# UBC-Thunderbots_PCB_Power__archive_power.net
KiCad netlist of a schematic drawn in Altium Designer
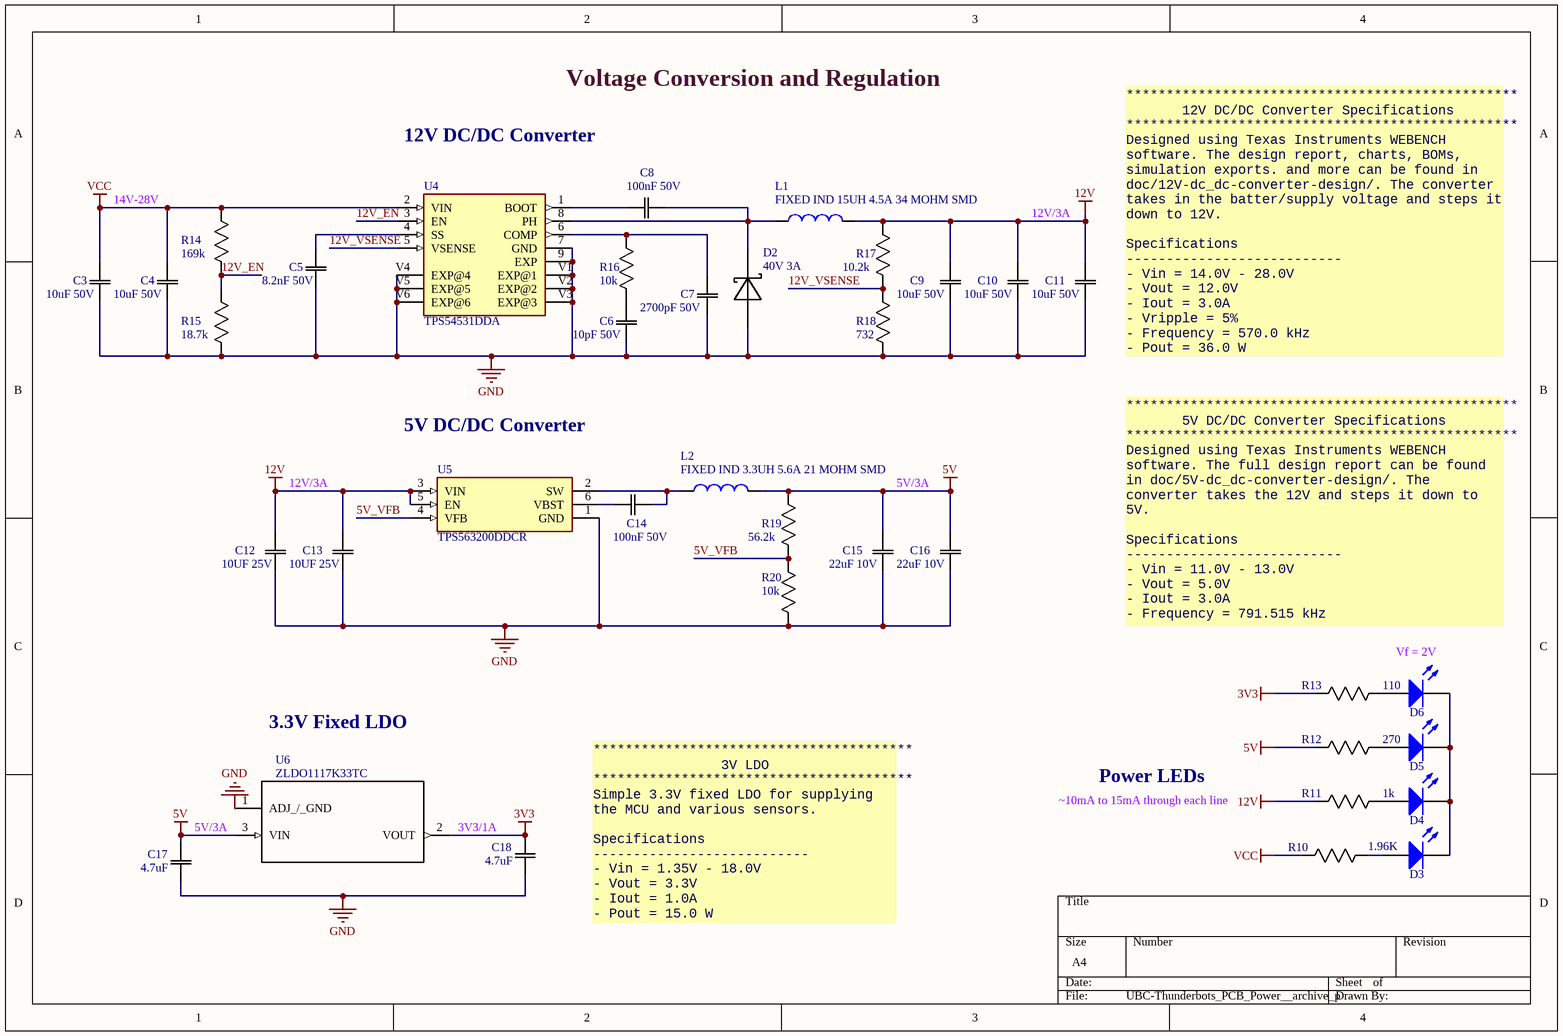
[diagram p0: UBC-Thunderbots_PCB_Power__archive_power-v2.1_pcb__regulation.SchDoc]

(export (version "E")
  (design (tool "Eeschema 10.0.6"))
  (components
    (comp (ref "C3")
      (value "10uF 50V")
      (footprint "1210")
      (description "CAP CER 10UF 50V X7R")
      (fields (field (name "TOLERANCE") "10%"))
      (libsource (lib "AltiumLibraries") (part "CAP 10uF 50V"))
    )
    (comp (ref "C4")
      (value "10uF 50V")
      (footprint "1210")
      (description "CAP CER 10UF 50V X7R")
      (fields (field (name "TOLERANCE") "10%"))
      (libsource (lib "AltiumLibraries") (part "CAP 10uF 50V"))
    )
    (comp (ref "C5")
      (value "8.2nF 50V")
      (footprint "0805")
      (description "CAP CER 8200PF 50V X7R 0805")
      (fields (field (name "TOLERANCE") "10%"))
      (libsource (lib "AltiumLibraries") (part "CAP 8.2nF 50V"))
    )
    (comp (ref "C6")
      (value "10pF 50V")
      (footprint "0603")
      (description "CAP CER 10PF 50V X7R 0603")
      (fields (field (name "TOLERANCE") "10%"))
      (libsource (lib "AltiumLibraries") (part "CAP 10pF 50V"))
    )
    (comp (ref "C7")
      (value "2700pF 50V")
      (footprint "0805")
      (description "CAP CER 2700PF 50V X7R 0805")
      (fields (field (name "TOLERANCE") "10%"))
      (libsource (lib "AltiumLibraries") (part "CAP 2700pF 50V"))
    )
    (comp (ref "C8")
      (value "100nF 50V")
      (footprint "0805")
      (description "CAP CER 0.1UF 50V X7R 0805")
      (fields (field (name "TOLERANCE") "10%"))
      (libsource (lib "AltiumLibraries") (part "CAP 100nF 50V"))
    )
    (comp (ref "C9")
      (value "10uF 50V")
      (footprint "1210")
      (description "CAP CER 10UF 50V X7R")
      (fields (field (name "TOLERANCE") "10%"))
      (libsource (lib "AltiumLibraries") (part "CAP 10uF 50V"))
    )
    (comp (ref "C10")
      (value "10uF 50V")
      (footprint "1210")
      (description "CAP CER 10UF 50V X7R")
      (fields (field (name "TOLERANCE") "10%"))
      (libsource (lib "AltiumLibraries") (part "CAP 10uF 50V"))
    )
    (comp (ref "C11")
      (value "10uF 50V")
      (footprint "1210")
      (description "CAP CER 10UF 50V X7R")
      (fields (field (name "TOLERANCE") "10%"))
      (libsource (lib "AltiumLibraries") (part "CAP 10uF 50V"))
    )
    (comp (ref "C12")
      (value "10UF 25V")
      (footprint "1206")
      (description "CAP CER 10UF 25V X5R 1206")
      (fields (field (name "TOLERANCE") "10%"))
      (libsource (lib "AltiumLibraries") (part "CAP 10uF 25V"))
    )
    (comp (ref "C13")
      (value "10UF 25V")
      (footprint "1206")
      (description "CAP CER 10UF 25V X5R 1206")
      (fields (field (name "TOLERANCE") "10%"))
      (libsource (lib "AltiumLibraries") (part "CAP 10uF 25V"))
    )
    (comp (ref "C14")
      (value "100nF 50V")
      (footprint "0805")
      (description "CAP CER 0.1UF 50V X7R 0805")
      (fields (field (name "TOLERANCE") "10%"))
      (libsource (lib "AltiumLibraries") (part "CAP 100nF 50V"))
    )
    (comp (ref "C15")
      (value "22uF 10V")
      (footprint "0805")
      (description "CAP CER 2.2UF 10V X5R 0805")
      (fields (field (name "TOLERANCE") "20%"))
      (libsource (lib "AltiumLibraries") (part "CAP 22uF 10V"))
    )
    (comp (ref "C16")
      (value "22uF 10V")
      (footprint "0805")
      (description "CAP CER 2.2UF 10V X5R 0805")
      (fields (field (name "TOLERANCE") "20%"))
      (libsource (lib "AltiumLibraries") (part "CAP 22uF 10V"))
    )
    (comp (ref "C17")
      (value "4.7uF")
      (footprint "0805")
      (description "CAP CER 4.7UF 25V X5R 0805")
      (fields (field (name "MP") "CL21B475KOFNNNE") (field (name "MF") "Samsung Electro-Mechanics"))
      (libsource (lib "AltiumLibraries") (part "CAP 4.7uF 0805"))
    )
    (comp (ref "C18")
      (value "4.7uF")
      (footprint "0805")
      (description "CAP CER 4.7UF 25V X5R 0805")
      (fields (field (name "MP") "CL21B475KOFNNNE") (field (name "MF") "Samsung Electro-Mechanics"))
      (libsource (lib "AltiumLibraries") (part "CAP 4.7uF 0805"))
    )
    (comp (ref "D2")
      (value "40V 3A")
      (footprint "DO-214AC")
      (description "Diode Schottky 40V 3A Surface Mount SMA")
      (libsource (lib "AltiumLibraries") (part "DIODE SCHOTTKY 40V 3A"))
    )
    (comp (ref "D3")
      (value "LED2")
      (footprint "3.2X1.6X1.1")
      (description "Typical RED, GREEN, YELLOW, AMBER GaAs LED")
      (libsource (lib "AltiumLibraries") (part "LED GREEN SMD"))
    )
    (comp (ref "D4")
      (value "LED2")
      (footprint "3.2X1.6X1.1")
      (description "Typical RED, GREEN, YELLOW, AMBER GaAs LED")
      (libsource (lib "AltiumLibraries") (part "LED GREEN SMD"))
    )
    (comp (ref "D5")
      (value "LED2")
      (footprint "3.2X1.6X1.1")
      (description "Typical RED, GREEN, YELLOW, AMBER GaAs LED")
      (libsource (lib "AltiumLibraries") (part "LED GREEN SMD"))
    )
    (comp (ref "D6")
      (value "LED2")
      (footprint "3.2X1.6X1.1")
      (description "Typical RED, GREEN, YELLOW, AMBER GaAs LED")
      (libsource (lib "AltiumLibraries") (part "LED GREEN SMD"))
    )
    (comp (ref "L1")
      (value "FIXED IND 15UH 4.5A 34 MOHM SMD")
      (description "15µH Unshielded Wirewound Inductor 4.5A 34mOhm Max Nonstandard")
      (fields (field (name "MP") "SDR1307-150ML") (field (name "MF") "Bourns Inc."))
      (libsource (lib "AltiumLibraries") (part "SDR1307-150ML"))
    )
    (comp (ref "L2")
      (value "FIXED IND 3.3UH 5.6A 21 MOHM SMD")
      (description "3.3µH Semi-Shielded Wirewound Inductor 5.6A 21mOhm Max Nonstandard")
      (fields (field (name "MP") "SRN8040-3R3Y") (field (name "MF") "Bourns Inc."))
      (libsource (lib "AltiumLibraries") (part "SRN8040-3R3Y"))
    )
    (comp (ref "R10")
      (value "1.96K")
      (footprint "0805")
      (description "RES SMD 1.96K OHM 1% 1/8W 0805")
      (fields (field (name "TOLERANCE") "1%"))
      (libsource (lib "AltiumLibraries") (part "RES 1.96k 1/8W"))
    )
    (comp (ref "R11")
      (value "1k")
      (footprint "0805")
      (description "RES SMD 1K OHM 5% 1/8W 0805")
      (fields (field (name "TOLERANCE") "5%"))
      (libsource (lib "AltiumLibraries") (part "RES 1k 1/8W"))
    )
    (comp (ref "R12")
      (value "270")
      (footprint "0805")
      (description "RES SMD 270 OHM 5% 1/8W 0805")
      (fields (field (name "TOLERANCE") "5%"))
      (libsource (lib "AltiumLibraries") (part "RES 270 1/8W"))
    )
    (comp (ref "R13")
      (value "110")
      (footprint "0805")
      (description "RES SMD 110 OHM 1% 1/8W 0805")
      (fields (field (name "TOLERANCE") "1%"))
      (libsource (lib "AltiumLibraries") (part "RES 110 1/8W"))
    )
    (comp (ref "R14")
      (value "169k")
      (footprint "0805")
      (description "RES SMD 169K OHM 1% 1/8W 0805")
      (fields (field (name "TOLERANCE") "1%"))
      (libsource (lib "AltiumLibraries") (part "RES 169k 1/8W"))
    )
    (comp (ref "R15")
      (value "18.7k")
      (footprint "1206")
      (description "RES SMD 18.7K OHM 1% 1/8W")
      (fields (field (name "TOLERANCE") "1%"))
      (libsource (lib "AltiumLibraries") (part "RES 18.7K OHM 1/8W"))
    )
    (comp (ref "R16")
      (value "10k")
      (footprint "0805")
      (description "RES SMD 10K OHM 1% 1/8W 0805")
      (fields (field (name "TOLERANCE") "1%"))
      (libsource (lib "AltiumLibraries") (part "RES 10k 1/8W"))
    )
    (comp (ref "R17")
      (value "10.2k")
      (footprint "0805")
      (description "RES SMD 10.2K OHM 1% 1/8W 0805")
      (fields (field (name "TOLERANCE") "1%"))
      (libsource (lib "AltiumLibraries") (part "RES 10.2k 1/8W"))
    )
    (comp (ref "R18")
      (value "732")
      (footprint "0805")
      (description "RES SMD 732 OHM 1% 1/8W 0805")
      (fields (field (name "TOLERANCE") "1%"))
      (libsource (lib "AltiumLibraries") (part "RES 732 1/8W"))
    )
    (comp (ref "R19")
      (value "56.2k")
      (footprint "0603")
      (description "RES SMD 56.2K OHM 1% 1/10W 0603")
      (fields (field (name "TOLERANCE") "1%"))
      (libsource (lib "AltiumLibraries") (part "RES 56.2k 1/10W"))
    )
    (comp (ref "R20")
      (value "10k")
      (footprint "0805")
      (description "RES SMD 10K OHM 1% 1/8W 0805")
      (fields (field (name "TOLERANCE") "1%"))
      (libsource (lib "AltiumLibraries") (part "RES 10k 1/8W"))
    )
    (comp (ref "U4")
      (value "TPS54531DDA")
      (footprint "8-PowerSOIC")
      (description "Buck Switching Regulator IC Positive Adjustable 0.8V 1 Output 5A 8-PowerSOIC _0.154, 3.90mm Width_")
      (fields (field (name "MF") "Texas Instruments"))
      (libsource (lib "AltiumLibraries") (part "TPS54531DDA"))
    )
    (comp (ref "U5")
      (value "TPS563200DDCR")
      (footprint "TSOT-23-6")
      (description "Buck Switching Regulator IC Positive Adjustable 0.76V 1 Output 3A SOT-23-6 Thin, TSOT-23-6")
      (fields (field (name "MF") "Texas Instruments"))
      (libsource (lib "AltiumLibraries") (part "TPS563200DDCR"))
    )
    (comp (ref "U6")
      (value "ZLDO1117K33TC")
      (footprint "TO-252-3")
      (description "Linear Voltage Regulator IC Positive Fixed 1 Output  1A TO-252-3")
      (fields (field (name "MF") "Diodes Incorporated"))
      (libsource (lib "AltiumLibraries") (part "ZLDO1117K33TC"))
    )
  )
  (nets
    (net (code "1") (name "/5V_VFB") (class "Default")
      (node (ref "R19") (pin "2") (pinfunction "R2_2") (pintype "passive"))
      (node (ref "R20") (pin "2") (pinfunction "R2_2") (pintype "passive"))
      (node (ref "U5") (pin "4") (pinfunction "VFB_4") (pintype "input"))
    )
    (net (code "2") (name "/12V_EN") (class "Default")
      (node (ref "R14") (pin "2") (pinfunction "R2_2") (pintype "passive"))
      (node (ref "R15") (pin "1") (pinfunction "R1_1") (pintype "passive"))
      (node (ref "U4") (pin "3") (pinfunction "EN_3") (pintype "input"))
    )
    (net (code "3") (name "/12V_VSENSE") (class "Default")
      (node (ref "R17") (pin "1") (pinfunction "R1_1") (pintype "passive"))
      (node (ref "R18") (pin "2") (pinfunction "R2_2") (pintype "passive"))
      (node (ref "U4") (pin "5") (pinfunction "VSENSE_5") (pintype "input"))
    )
    (net (code "4") (name "3V3") (class "Default")
      (node (ref "C18") (pin "2") (pinfunction "C2_2") (pintype "passive"))
      (node (ref "R13") (pin "1") (pinfunction "R1_1") (pintype "passive"))
      (node (ref "U6") (pin "2") (pinfunction "VOUT_2") (pintype "output"))
    )
    (net (code "5") (name "5V") (class "Default")
      (node (ref "C15") (pin "2") (pinfunction "C2_2") (pintype "passive"))
      (node (ref "C16") (pin "2") (pinfunction "C2_2") (pintype "passive"))
      (node (ref "C17") (pin "2") (pinfunction "C2_2") (pintype "passive"))
      (node (ref "L2") (pin "2") (pinfunction "2_2") (pintype "passive"))
      (node (ref "R12") (pin "1") (pinfunction "R1_1") (pintype "passive"))
      (node (ref "R19") (pin "1") (pinfunction "R1_1") (pintype "passive"))
      (node (ref "U6") (pin "3") (pinfunction "VIN_3") (pintype "input"))
    )
    (net (code "6") (name "12V") (class "Default")
      (node (ref "C10") (pin "2") (pinfunction "C2_2") (pintype "passive"))
      (node (ref "C11") (pin "2") (pinfunction "C2_2") (pintype "passive"))
      (node (ref "C12") (pin "2") (pinfunction "C2_2") (pintype "passive"))
      (node (ref "C13") (pin "2") (pinfunction "C2_2") (pintype "passive"))
      (node (ref "C9") (pin "2") (pinfunction "C2_2") (pintype "passive"))
      (node (ref "L1") (pin "2") (pinfunction "2_2") (pintype "passive"))
      (node (ref "R11") (pin "1") (pinfunction "R1_1") (pintype "passive"))
      (node (ref "R17") (pin "2") (pinfunction "R2_2") (pintype "passive"))
      (node (ref "U5") (pin "3") (pinfunction "VIN_3") (pintype "input"))
      (node (ref "U5") (pin "5") (pinfunction "EN_5") (pintype "input"))
    )
    (net (code "7") (name "GND") (class "Default")
      (node (ref "C10") (pin "1") (pinfunction "C1_1") (pintype "passive"))
      (node (ref "C11") (pin "1") (pinfunction "C1_1") (pintype "passive"))
      (node (ref "C12") (pin "1") (pinfunction "C1_1") (pintype "passive"))
      (node (ref "C13") (pin "1") (pinfunction "C1_1") (pintype "passive"))
      (node (ref "C15") (pin "1") (pinfunction "C1_1") (pintype "passive"))
      (node (ref "C16") (pin "1") (pinfunction "C1_1") (pintype "passive"))
      (node (ref "C17") (pin "1") (pinfunction "C1_1") (pintype "passive"))
      (node (ref "C18") (pin "1") (pinfunction "C1_1") (pintype "passive"))
      (node (ref "C3") (pin "1") (pinfunction "C1_1") (pintype "passive"))
      (node (ref "C4") (pin "1") (pinfunction "C1_1") (pintype "passive"))
      (node (ref "C5") (pin "1") (pinfunction "C1_1") (pintype "passive"))
      (node (ref "C6") (pin "1") (pinfunction "C1_1") (pintype "passive"))
      (node (ref "C7") (pin "1") (pinfunction "C1_1") (pintype "passive"))
      (node (ref "C9") (pin "1") (pinfunction "C1_1") (pintype "passive"))
      (node (ref "D2") (pin "A") (pinfunction "A_A") (pintype "passive"))
      (node (ref "R15") (pin "2") (pinfunction "R2_2") (pintype "passive"))
      (node (ref "R18") (pin "1") (pinfunction "R1_1") (pintype "passive"))
      (node (ref "R20") (pin "1") (pinfunction "R1_1") (pintype "passive"))
      (node (ref "U4") (pin "7") (pinfunction "GND_7") (pintype "power_in"))
      (node (ref "U4") (pin "9") (pinfunction "EXP_9") (pintype "power_in"))
      (node (ref "U4") (pin "V1") (pinfunction "EXP@1_V1") (pintype "power_in"))
      (node (ref "U4") (pin "V2") (pinfunction "EXP@2_V2") (pintype "power_in"))
      (node (ref "U4") (pin "V3") (pinfunction "EXP@3_V3") (pintype "power_in"))
      (node (ref "U4") (pin "V4") (pinfunction "EXP@4_V4") (pintype "power_in"))
      (node (ref "U4") (pin "V5") (pinfunction "EXP@5_V5") (pintype "power_in"))
      (node (ref "U4") (pin "V6") (pinfunction "EXP@6_V6") (pintype "power_in"))
      (node (ref "U5") (pin "1") (pinfunction "GND_1") (pintype "power_in"))
      (node (ref "U6") (pin "1") (pinfunction "ADJ_/_GND_1") (pintype "power_in"))
    )
    (net (code "8") (name "Net-(C5-C2)") (class "Default")
      (node (ref "C5") (pin "2") (pinfunction "C2_2") (pintype "passive"))
      (node (ref "U4") (pin "4") (pinfunction "SS_4") (pintype "input"))
    )
    (net (code "9") (name "Net-(C6-C2)") (class "Default")
      (node (ref "C6") (pin "2") (pinfunction "C2_2") (pintype "passive"))
      (node (ref "R16") (pin "2") (pinfunction "R2_2") (pintype "passive"))
    )
    (net (code "10") (name "Net-(C7-C2)") (class "Default")
      (node (ref "C7") (pin "2") (pinfunction "C2_2") (pintype "passive"))
      (node (ref "R16") (pin "1") (pinfunction "R1_1") (pintype "passive"))
      (node (ref "U4") (pin "6") (pinfunction "COMP_6") (pintype "output"))
    )
    (net (code "11") (name "Net-(C8-C1)") (class "Default")
      (node (ref "C8") (pin "1") (pinfunction "C1_1") (pintype "passive"))
      (node (ref "U4") (pin "1") (pinfunction "BOOT_1") (pintype "output"))
    )
    (net (code "12") (name "Net-(C8-C2)") (class "Default")
      (node (ref "C8") (pin "2") (pinfunction "C2_2") (pintype "passive"))
      (node (ref "D2") (pin "C") (pinfunction "K_C") (pintype "passive"))
      (node (ref "L1") (pin "1") (pinfunction "1_1") (pintype "passive"))
      (node (ref "U4") (pin "8") (pinfunction "PH_8") (pintype "output"))
    )
    (net (code "13") (name "Net-(C14-C1)") (class "Default")
      (node (ref "C14") (pin "1") (pinfunction "C1_1") (pintype "passive"))
      (node (ref "U5") (pin "6") (pinfunction "VBST_6") (pintype "passive"))
    )
    (net (code "14") (name "Net-(C14-C2)") (class "Default")
      (node (ref "C14") (pin "2") (pinfunction "C2_2") (pintype "passive"))
      (node (ref "L2") (pin "1") (pinfunction "1_1") (pintype "passive"))
      (node (ref "U5") (pin "2") (pinfunction "SW_2") (pintype "passive"))
    )
    (net (code "15") (name "Net-(D3-A)") (class "Default")
      (node (ref "D3") (pin "1") (pinfunction "A_1") (pintype "passive"))
      (node (ref "R10") (pin "2") (pinfunction "R2_2") (pintype "passive"))
    )
    (net (code "16") (name "Net-(D3-K)") (class "Default")
      (node (ref "D3") (pin "2") (pinfunction "K_2") (pintype "passive"))
      (node (ref "D4") (pin "2") (pinfunction "K_2") (pintype "passive"))
      (node (ref "D5") (pin "2") (pinfunction "K_2") (pintype "passive"))
      (node (ref "D6") (pin "2") (pinfunction "K_2") (pintype "passive"))
    )
    (net (code "17") (name "Net-(D4-A)") (class "Default")
      (node (ref "D4") (pin "1") (pinfunction "A_1") (pintype "passive"))
      (node (ref "R11") (pin "2") (pinfunction "R2_2") (pintype "passive"))
    )
    (net (code "18") (name "Net-(D5-A)") (class "Default")
      (node (ref "D5") (pin "1") (pinfunction "A_1") (pintype "passive"))
      (node (ref "R12") (pin "2") (pinfunction "R2_2") (pintype "passive"))
    )
    (net (code "19") (name "Net-(D6-A)") (class "Default")
      (node (ref "D6") (pin "1") (pinfunction "A_1") (pintype "passive"))
      (node (ref "R13") (pin "2") (pinfunction "R2_2") (pintype "passive"))
    )
    (net (code "20") (name "VCC") (class "Default")
      (node (ref "C3") (pin "2") (pinfunction "C2_2") (pintype "passive"))
      (node (ref "C4") (pin "2") (pinfunction "C2_2") (pintype "passive"))
      (node (ref "R10") (pin "1") (pinfunction "R1_1") (pintype "passive"))
      (node (ref "R14") (pin "1") (pinfunction "R1_1") (pintype "passive"))
      (node (ref "U4") (pin "2") (pinfunction "VIN_2") (pintype "input"))
    )
  )
)
